# OLC.net
KiCad netlist of a schematic drawn in EAGLE
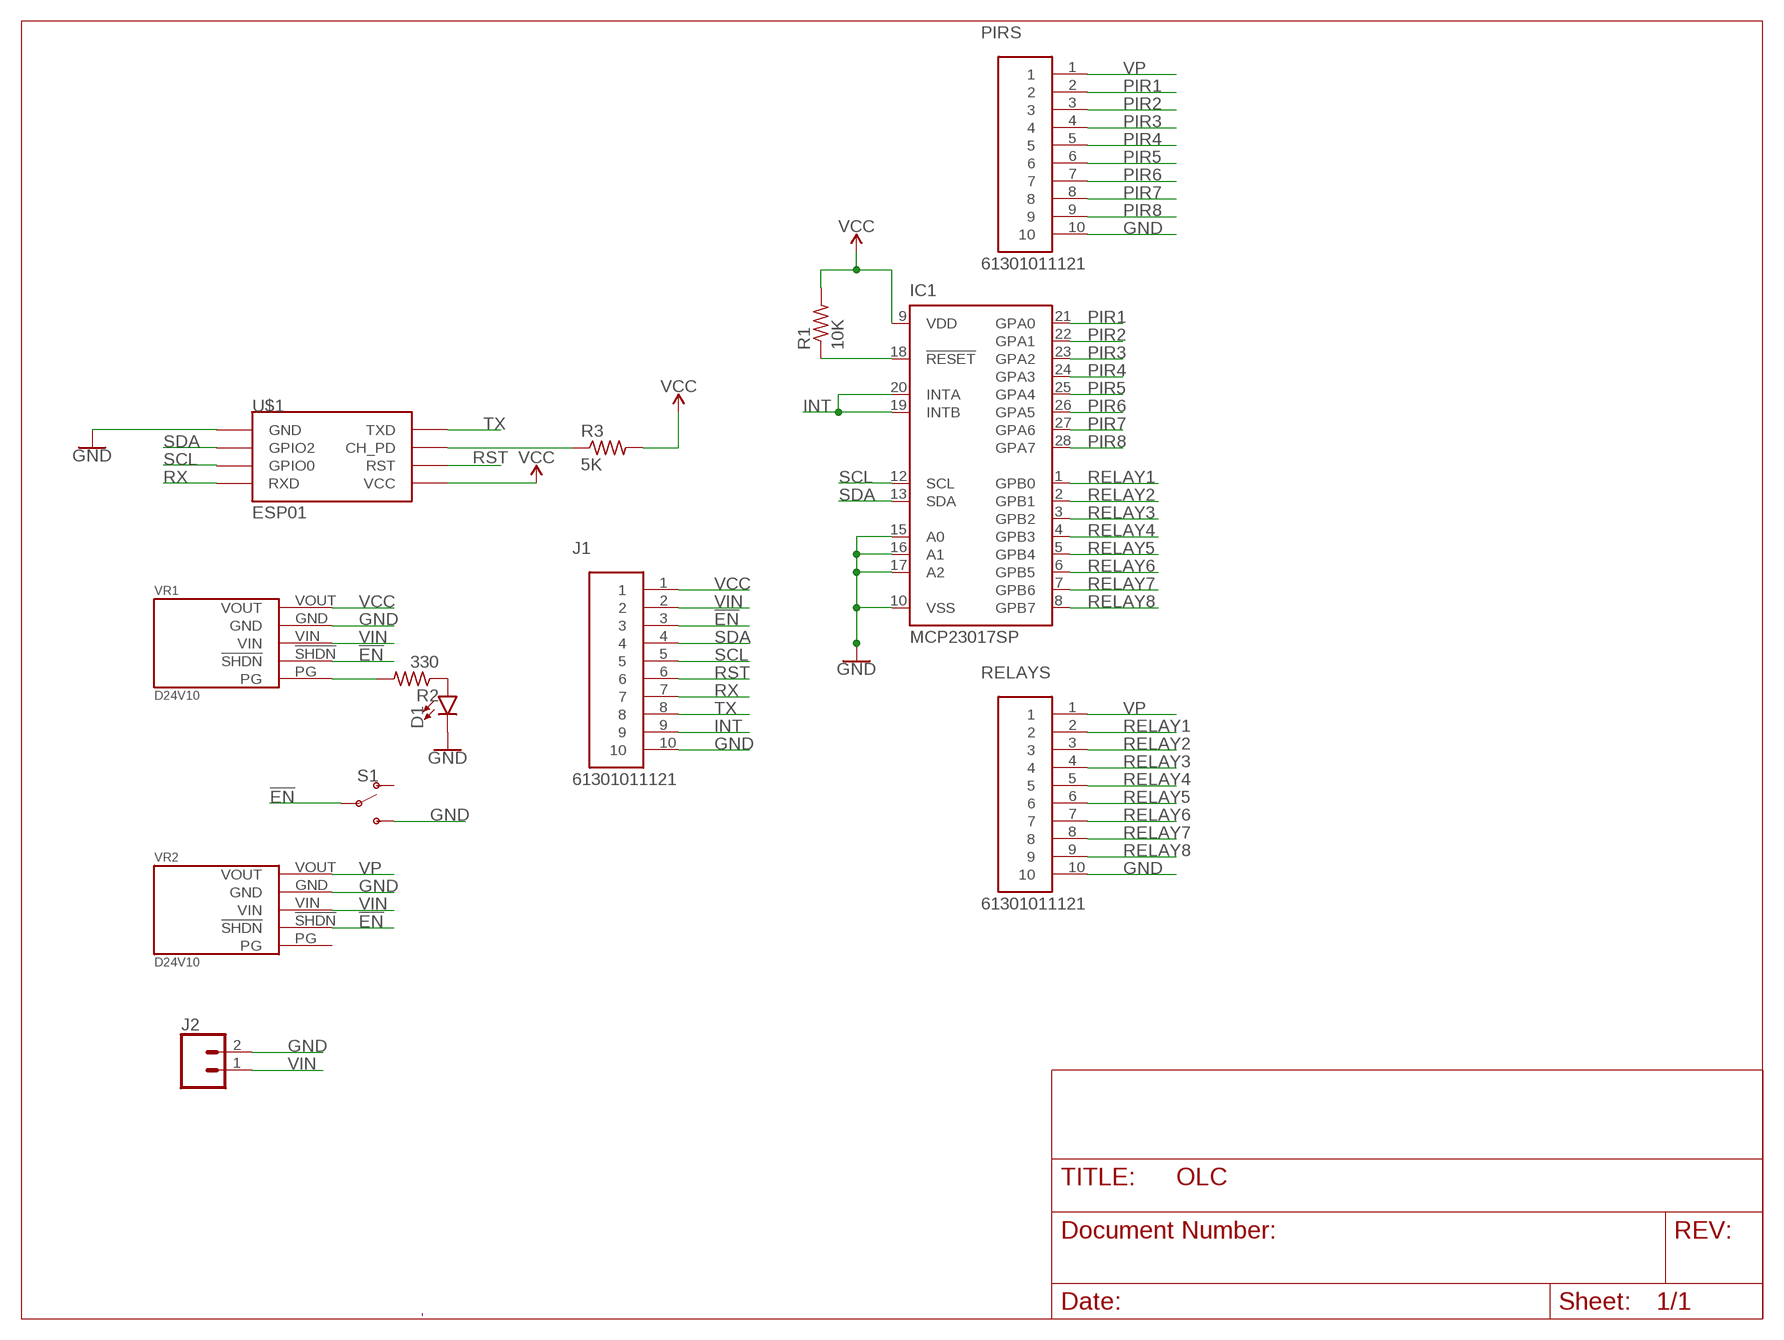
[diagram p0: schematic, sheet 1]

(export (version "E")
  (design (tool "Eeschema 10.0.6"))
  (components
    (comp (ref "D1")
      (value "LED5MM-KIT")
      (footprint "eagle-import:LED_5MM-KIT")
      (libsource (lib "eagle-import") (part "LED5MM-KIT"))
    )
    (comp (ref "IC1")
      (value "MCP23017SP")
      (footprint "eagle-import:DIL28-3")
      (fields (field (name "MF") "MICROCHIP") (field (name "MPN") "MCP23017-E/SP"))
      (libsource (lib "eagle-import") (part "MCP23017SP"))
    )
    (comp (ref "J1")
      (value "61301011121")
      (footprint "eagle-import:61301011121")
      (fields
        (field (name "DIGIKEY_PART_NUMBER") "732-2670-ND")
        (field (name "MANUFACTURER") "Wurth Electronics Inc.")
        (field (name "CREATED_BY") "PCBLayout.com")
      )
      (libsource (lib "eagle-import") (part "61301011121"))
    )
    (comp (ref "J2")
      (value "CONN_023.5MM")
      (footprint "eagle-import:SCREWTERMINAL-3.5MM-2")
      (libsource (lib "eagle-import") (part "CONN_023.5MM"))
    )
    (comp (ref "PIRS")
      (value "61301011121")
      (footprint "eagle-import:61301011121")
      (fields
        (field (name "DIGIKEY_PART_NUMBER") "732-2670-ND")
        (field (name "MANUFACTURER") "Wurth Electronics Inc.")
        (field (name "CREATED_BY") "PCBLayout.com")
      )
      (libsource (lib "eagle-import") (part "61301011121"))
    )
    (comp (ref "R1")
      (value "10K")
      (footprint "eagle-import:0207_10")
      (libsource (lib "eagle-import") (part "R-US_0207/10"))
    )
    (comp (ref "R2")
      (value "330")
      (footprint "eagle-import:0207_10")
      (libsource (lib "eagle-import") (part "R-US_0207/10"))
    )
    (comp (ref "R3")
      (value "5K")
      (footprint "eagle-import:0207_10")
      (libsource (lib "eagle-import") (part "R-US_0207/10"))
    )
    (comp (ref "RELAYS")
      (value "61301011121")
      (footprint "eagle-import:61301011121")
      (fields
        (field (name "DIGIKEY_PART_NUMBER") "732-2670-ND")
        (field (name "MANUFACTURER") "Wurth Electronics Inc.")
        (field (name "CREATED_BY") "PCBLayout.com")
      )
      (libsource (lib "eagle-import") (part "61301011121"))
    )
    (comp (ref "S1")
      (value "SWITCH-SPDT-PTH-11.6X4.0MM")
      (footprint "eagle-import:SWITCH_SPDT_PTH_11.6X4.0MM")
      (libsource (lib "eagle-import") (part "SWITCH-SPDT-PTH-11.6X4.0MM"))
    )
    (comp (ref "U$1")
      (value "ESP01")
      (footprint "eagle-import:ESP01")
      (libsource (lib "eagle-import") (part "ESP01"))
    )
    (comp (ref "VR1")
      (value "D24V10")
      (footprint "eagle-import:D24V10")
      (libsource (lib "eagle-import") (part "D24V10"))
    )
    (comp (ref "VR2")
      (value "D24V10")
      (footprint "eagle-import:D24V10")
      (libsource (lib "eagle-import") (part "D24V10"))
    )
  )
  (nets
    (net (code "1") (name "/INT") (class "Default")
      (node (ref "IC1") (pin "19") (pinfunction "INTB_19") (pintype "output"))
      (node (ref "IC1") (pin "20") (pinfunction "INTA_20") (pintype "output"))
      (node (ref "J1") (pin "9") (pinfunction "9_9") (pintype "passive"))
    )
    (net (code "2") (name "/PIR1") (class "Default")
      (node (ref "IC1") (pin "21") (pinfunction "GPA0_21") (pintype "bidirectional"))
      (node (ref "PIRS") (pin "2") (pinfunction "2_2") (pintype "passive"))
    )
    (net (code "3") (name "/PIR2") (class "Default")
      (node (ref "IC1") (pin "22") (pinfunction "GPA1_22") (pintype "bidirectional"))
      (node (ref "PIRS") (pin "3") (pinfunction "3_3") (pintype "passive"))
    )
    (net (code "4") (name "/PIR3") (class "Default")
      (node (ref "IC1") (pin "23") (pinfunction "GPA2_23") (pintype "bidirectional"))
      (node (ref "PIRS") (pin "4") (pinfunction "4_4") (pintype "passive"))
    )
    (net (code "5") (name "/PIR4") (class "Default")
      (node (ref "IC1") (pin "24") (pinfunction "GPA3_24") (pintype "bidirectional"))
      (node (ref "PIRS") (pin "5") (pinfunction "5_5") (pintype "passive"))
    )
    (net (code "6") (name "/PIR5") (class "Default")
      (node (ref "IC1") (pin "25") (pinfunction "GPA4_25") (pintype "bidirectional"))
      (node (ref "PIRS") (pin "6") (pinfunction "6_6") (pintype "passive"))
    )
    (net (code "7") (name "/PIR6") (class "Default")
      (node (ref "IC1") (pin "26") (pinfunction "GPA5_26") (pintype "bidirectional"))
      (node (ref "PIRS") (pin "7") (pinfunction "7_7") (pintype "passive"))
    )
    (net (code "8") (name "/PIR7") (class "Default")
      (node (ref "IC1") (pin "27") (pinfunction "GPA6_27") (pintype "bidirectional"))
      (node (ref "PIRS") (pin "8") (pinfunction "8_8") (pintype "passive"))
    )
    (net (code "9") (name "/PIR8") (class "Default")
      (node (ref "IC1") (pin "28") (pinfunction "GPA7_28") (pintype "bidirectional"))
      (node (ref "PIRS") (pin "9") (pinfunction "9_9") (pintype "passive"))
    )
    (net (code "10") (name "/RELAY1") (class "Default")
      (node (ref "IC1") (pin "1") (pinfunction "GPB0_1") (pintype "bidirectional"))
      (node (ref "RELAYS") (pin "2") (pinfunction "2_2") (pintype "passive"))
    )
    (net (code "11") (name "/RELAY2") (class "Default")
      (node (ref "IC1") (pin "2") (pinfunction "GPB1_2") (pintype "bidirectional"))
      (node (ref "RELAYS") (pin "3") (pinfunction "3_3") (pintype "passive"))
    )
    (net (code "12") (name "/RELAY3") (class "Default")
      (node (ref "IC1") (pin "3") (pinfunction "GPB2_3") (pintype "bidirectional"))
      (node (ref "RELAYS") (pin "4") (pinfunction "4_4") (pintype "passive"))
    )
    (net (code "13") (name "/RELAY4") (class "Default")
      (node (ref "IC1") (pin "4") (pinfunction "GPB3_4") (pintype "bidirectional"))
      (node (ref "RELAYS") (pin "5") (pinfunction "5_5") (pintype "passive"))
    )
    (net (code "14") (name "/RELAY5") (class "Default")
      (node (ref "IC1") (pin "5") (pinfunction "GPB4_5") (pintype "bidirectional"))
      (node (ref "RELAYS") (pin "6") (pinfunction "6_6") (pintype "passive"))
    )
    (net (code "15") (name "/RELAY6") (class "Default")
      (node (ref "IC1") (pin "6") (pinfunction "GPB5_6") (pintype "bidirectional"))
      (node (ref "RELAYS") (pin "7") (pinfunction "7_7") (pintype "passive"))
    )
    (net (code "16") (name "/RELAY7") (class "Default")
      (node (ref "IC1") (pin "7") (pinfunction "GPB6_7") (pintype "bidirectional"))
      (node (ref "RELAYS") (pin "8") (pinfunction "8_8") (pintype "passive"))
    )
    (net (code "17") (name "/RELAY8") (class "Default")
      (node (ref "IC1") (pin "8") (pinfunction "GPB7_8") (pintype "bidirectional"))
      (node (ref "RELAYS") (pin "9") (pinfunction "9_9") (pintype "passive"))
    )
    (net (code "18") (name "/RST") (class "Default")
      (node (ref "J1") (pin "6") (pinfunction "6_6") (pintype "passive"))
      (node (ref "U$1") (pin "RST") (pinfunction "RST_RST") (pintype "bidirectional"))
    )
    (net (code "19") (name "/RX") (class "Default")
      (node (ref "J1") (pin "7") (pinfunction "7_7") (pintype "passive"))
      (node (ref "U$1") (pin "RX") (pinfunction "RXD_RX") (pintype "bidirectional"))
    )
    (net (code "20") (name "/SCL") (class "Default")
      (node (ref "IC1") (pin "12") (pinfunction "SCL_12") (pintype "input"))
      (node (ref "J1") (pin "5") (pinfunction "5_5") (pintype "passive"))
      (node (ref "U$1") (pin "GPIO0") (pinfunction "GPIO0_GPIO0") (pintype "bidirectional"))
    )
    (net (code "21") (name "/SDA") (class "Default")
      (node (ref "IC1") (pin "13") (pinfunction "SDA_13") (pintype "bidirectional"))
      (node (ref "J1") (pin "4") (pinfunction "4_4") (pintype "passive"))
      (node (ref "U$1") (pin "GPIO2") (pinfunction "GPIO2_GPIO2") (pintype "bidirectional"))
    )
    (net (code "22") (name "/TX") (class "Default")
      (node (ref "J1") (pin "8") (pinfunction "8_8") (pintype "passive"))
      (node (ref "U$1") (pin "TX") (pinfunction "TXD_TX") (pintype "bidirectional"))
    )
    (net (code "23") (name "/VIN") (class "Default")
      (node (ref "J1") (pin "2") (pinfunction "2_2") (pintype "passive"))
      (node (ref "J2") (pin "1") (pinfunction "1_1") (pintype "passive"))
      (node (ref "VR1") (pin "VIN") (pinfunction "VIN_VIN") (pintype "passive"))
      (node (ref "VR2") (pin "VIN") (pinfunction "VIN_VIN") (pintype "passive"))
    )
    (net (code "24") (name "/VP") (class "Default")
      (node (ref "PIRS") (pin "1") (pinfunction "1_1") (pintype "passive"))
      (node (ref "RELAYS") (pin "1") (pinfunction "1_1") (pintype "passive"))
      (node (ref "VR2") (pin "VOUT") (pinfunction "VOUT_VOUT") (pintype "passive"))
    )
    (net (code "25") (name "/~{EN}") (class "Default")
      (node (ref "J1") (pin "3") (pinfunction "3_3") (pintype "passive"))
      (node (ref "S1") (pin "2") (pinfunction "P_2") (pintype "passive"))
      (node (ref "VR1") (pin "!SHDN") (pinfunction "~{SHDN}_!SHDN") (pintype "input"))
      (node (ref "VR2") (pin "!SHDN") (pinfunction "~{SHDN}_!SHDN") (pintype "input"))
    )
    (net (code "26") (name "GND") (class "Default")
      (node (ref "D1") (pin "K") (pinfunction "C_K") (pintype "passive"))
      (node (ref "IC1") (pin "10") (pinfunction "VSS_10") (pintype "power_in"))
      (node (ref "IC1") (pin "15") (pinfunction "A0_15") (pintype "input"))
      (node (ref "IC1") (pin "16") (pinfunction "A1_16") (pintype "input"))
      (node (ref "IC1") (pin "17") (pinfunction "A2_17") (pintype "input"))
      (node (ref "J1") (pin "10") (pinfunction "10_10") (pintype "passive"))
      (node (ref "J2") (pin "2") (pinfunction "2_2") (pintype "passive"))
      (node (ref "PIRS") (pin "10") (pinfunction "10_10") (pintype "passive"))
      (node (ref "RELAYS") (pin "10") (pinfunction "10_10") (pintype "passive"))
      (node (ref "S1") (pin "3") (pinfunction "S_3") (pintype "passive"))
      (node (ref "U$1") (pin "GND") (pinfunction "GND_GND") (pintype "bidirectional"))
      (node (ref "VR1") (pin "GND") (pinfunction "GND_GND") (pintype "passive"))
      (node (ref "VR2") (pin "GND") (pinfunction "GND_GND") (pintype "passive"))
    )
    (net (code "27") (name "Net-(D1-PadA)") (class "Default")
      (node (ref "D1") (pin "A") (pinfunction "A_A") (pintype "passive"))
      (node (ref "R2") (pin "1") (pinfunction "1_1") (pintype "passive"))
    )
    (net (code "28") (name "Net-(IC1-~{RESET})") (class "Default")
      (node (ref "IC1") (pin "18") (pinfunction "~{RESET}_18") (pintype "input"))
      (node (ref "R1") (pin "1") (pinfunction "1_1") (pintype "passive"))
    )
    (net (code "29") (name "Net-(R2-Pad2)") (class "Default")
      (node (ref "R2") (pin "2") (pinfunction "2_2") (pintype "passive"))
      (node (ref "VR1") (pin "PG") (pinfunction "PG_PG") (pintype "output"))
    )
    (net (code "30") (name "Net-(R3-Pad1)") (class "Default")
      (node (ref "R3") (pin "1") (pinfunction "1_1") (pintype "passive"))
      (node (ref "U$1") (pin "CH_PD") (pinfunction "CH_PD_CH_PD") (pintype "bidirectional"))
    )
    (net (code "31") (name "VCC") (class "Default")
      (node (ref "IC1") (pin "9") (pinfunction "VDD_9") (pintype "power_in"))
      (node (ref "J1") (pin "1") (pinfunction "1_1") (pintype "passive"))
      (node (ref "R1") (pin "2") (pinfunction "2_2") (pintype "passive"))
      (node (ref "R3") (pin "2") (pinfunction "2_2") (pintype "passive"))
      (node (ref "U$1") (pin "VCC") (pinfunction "VCC_VCC") (pintype "bidirectional"))
      (node (ref "VR1") (pin "VOUT") (pinfunction "VOUT_VOUT") (pintype "passive"))
    )
    (net (code "32") (name "unconnected-(S1-O-Pad1)") (class "Default")
      (node (ref "S1") (pin "1") (pinfunction "O_1") (pintype "passive"))
    )
    (net (code "33") (name "unconnected-(VR2-PadPG)") (class "Default")
      (node (ref "VR2") (pin "PG") (pinfunction "PG_PG") (pintype "output"))
    )
  )
)
